# source_eagle.net
KiCad netlist of a schematic drawn in EAGLE
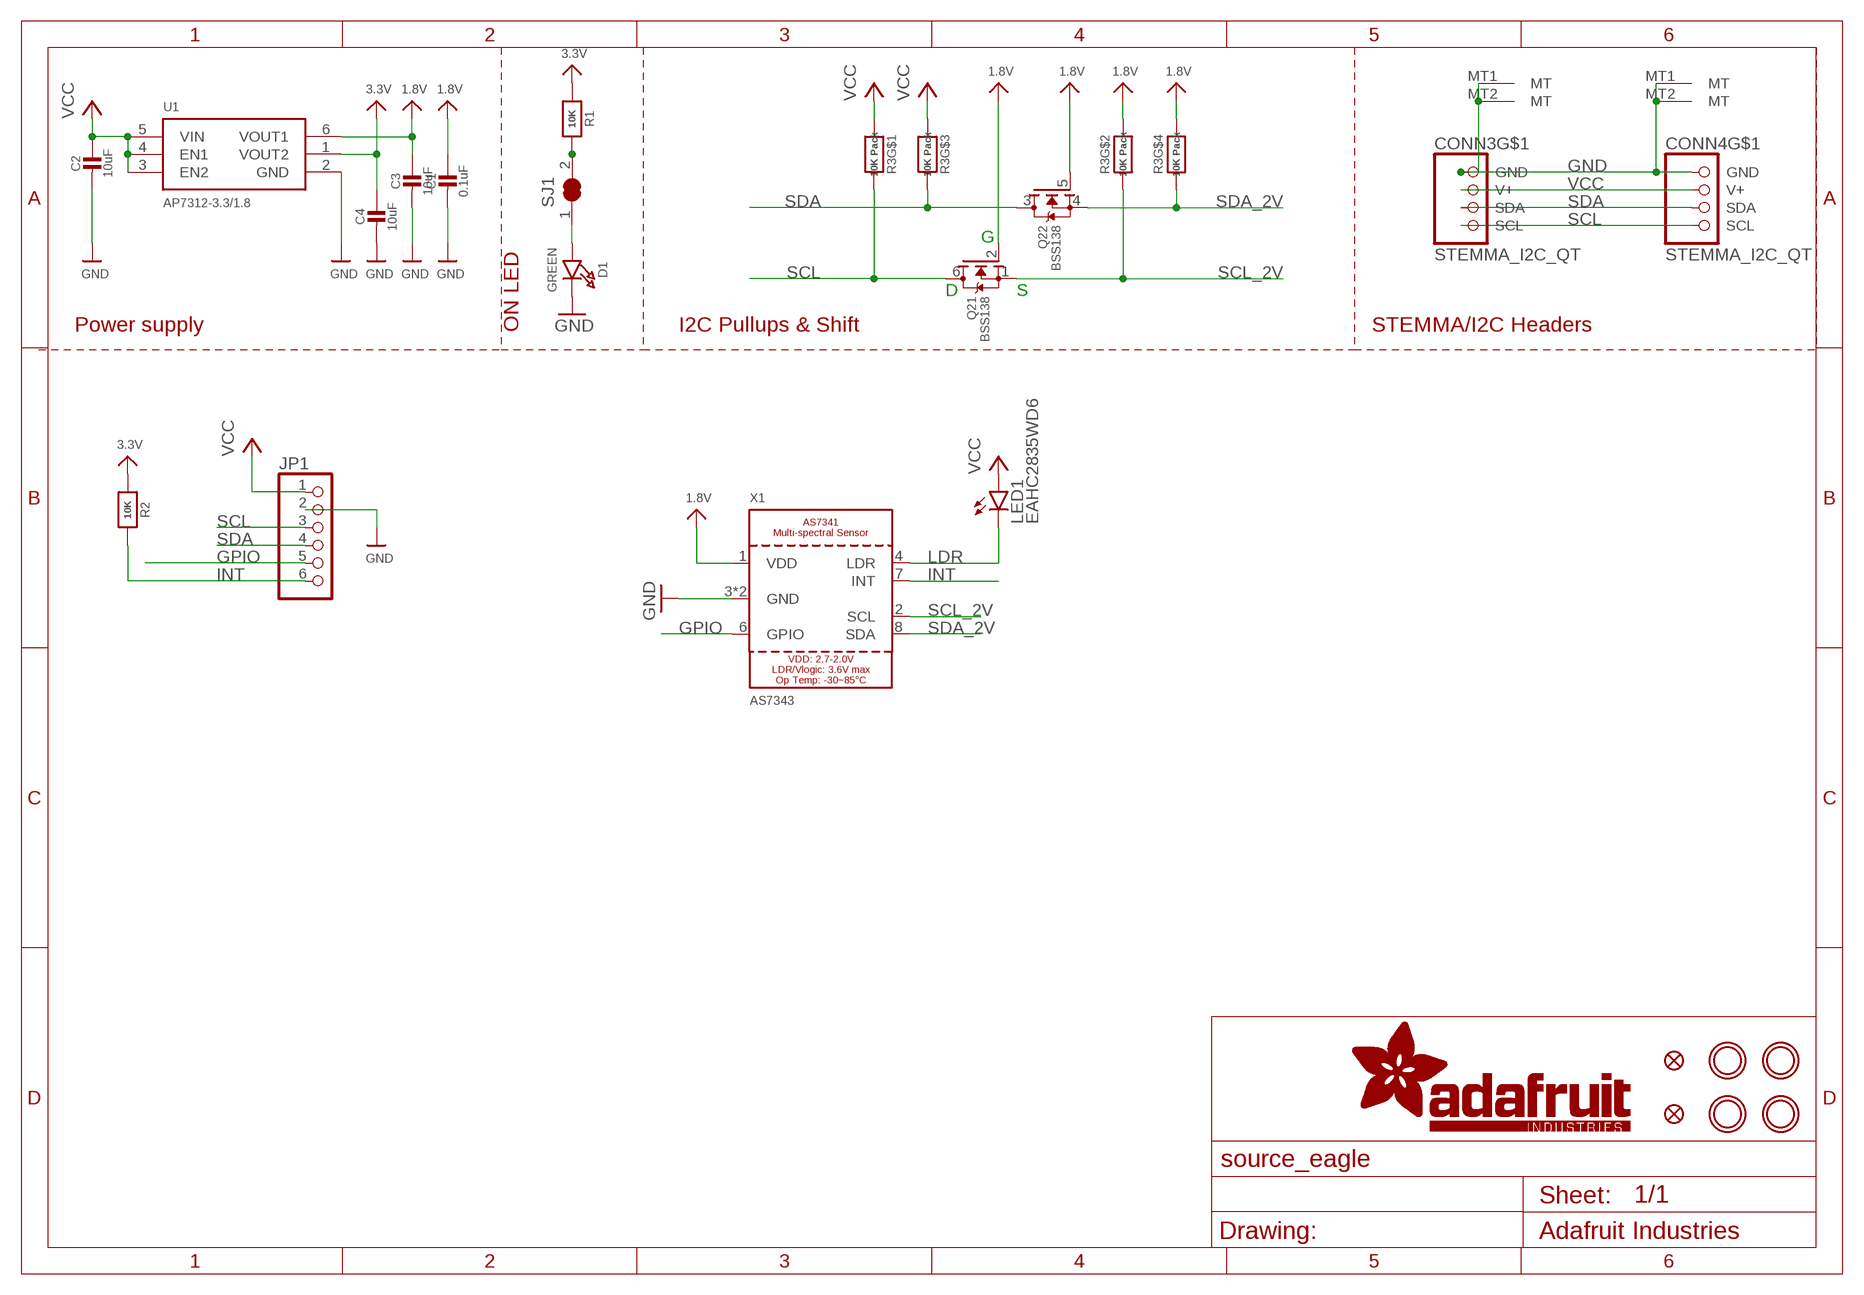
[diagram p0: schematic, sheet 1]

(export (version "E")
  (design (tool "Eeschema 10.0.6"))
  (components
    (comp (ref "C1")
      (value "0.1uF")
      (footprint "eagle-import:0603-NO")
      (libsource (lib "eagle-import") (part "CAP_CERAMIC0603_NO"))
    )
    (comp (ref "C2")
      (value "10uF")
      (footprint "eagle-import:0805-NO")
      (libsource (lib "eagle-import") (part "CAP_CERAMIC0805-NOOUTLINE"))
    )
    (comp (ref "C3")
      (value "10uF")
      (footprint "eagle-import:0805-NO")
      (libsource (lib "eagle-import") (part "CAP_CERAMIC0805-NOOUTLINE"))
    )
    (comp (ref "C4")
      (value "10uF")
      (footprint "eagle-import:0805-NO")
      (libsource (lib "eagle-import") (part "CAP_CERAMIC0805-NOOUTLINE"))
    )
    (comp (ref "CONN3")
      (value "STEMMA_I2C_QT")
      (footprint "eagle-import:JST_SH4")
      (libsource (lib "eagle-import") (part "STEMMA_I2C_QT"))
    )
    (comp (ref "CONN4")
      (value "STEMMA_I2C_QT")
      (footprint "eagle-import:JST_SH4")
      (libsource (lib "eagle-import") (part "STEMMA_I2C_QT"))
    )
    (comp (ref "D1")
      (value "GREEN")
      (footprint "eagle-import:CHIPLED_0603_NOOUTLINE")
      (libsource (lib "eagle-import") (part "LED0603_NOOUTLINE"))
    )
    (comp (ref "FID3")
      (value "FIDUCIAL_0.5MM")
      (footprint "eagle-import:FIDUCIAL_0.5MM")
      (libsource (lib "eagle-import") (part "FIDUCIAL_0.5MM"))
    )
    (comp (ref "FID4")
      (value "FIDUCIAL_0.5MM")
      (footprint "eagle-import:FIDUCIAL_0.5MM")
      (libsource (lib "eagle-import") (part "FIDUCIAL_0.5MM"))
    )
    (comp (ref "JP1")
      (value "HEADER-1X670MIL")
      (footprint "eagle-import:1X06_ROUND_70")
      (libsource (lib "eagle-import") (part "HEADER-1X670MIL"))
    )
    (comp (ref "LED1")
      (value "EAHC2835WD6")
      (footprint "eagle-import:KA-3528ASYC")
      (libsource (lib "eagle-import") (part "LEDKA-3528ASYC"))
    )
    (comp (ref "Q2")
      (value "BSS138")
      (footprint "eagle-import:SOT363")
      (libsource (lib "eagle-import") (part "MOSFET-N_DUAL"))
    )
    (comp (ref "R1")
      (value "10K")
      (footprint "eagle-import:0603-NO")
      (libsource (lib "eagle-import") (part "RESISTOR_0603_NOOUT"))
    )
    (comp (ref "R2")
      (value "10K")
      (footprint "eagle-import:0603-NO")
      (libsource (lib "eagle-import") (part "RESISTOR_0603_NOOUT"))
    )
    (comp (ref "R3")
      (value "10K Pack")
      (footprint "eagle-import:RESPACK_4X0603")
      (libsource (lib "eagle-import") (part "RESISTOR_4PACK"))
    )
    (comp (ref "SJ1")
      (value "SOLDERJUMPER_CLOSED")
      (footprint "eagle-import:SOLDERJUMPER_CLOSEDWIRE")
      (libsource (lib "eagle-import") (part "SOLDERJUMPER_CLOSED"))
    )
    (comp (ref "U$1")
      (value "MOUNTINGHOLE2.5")
      (footprint "eagle-import:MOUNTINGHOLE_2.5_PLATED")
      (libsource (lib "eagle-import") (part "MOUNTINGHOLE2.5"))
    )
    (comp (ref "U$17")
      (value "MOUNTINGHOLE2.5")
      (footprint "eagle-import:MOUNTINGHOLE_2.5_PLATED")
      (libsource (lib "eagle-import") (part "MOUNTINGHOLE2.5"))
    )
    (comp (ref "U$19")
      (value "MOUNTINGHOLE2.5")
      (footprint "eagle-import:MOUNTINGHOLE_2.5_PLATED")
      (libsource (lib "eagle-import") (part "MOUNTINGHOLE2.5"))
    )
    (comp (ref "U$21")
      (value "MOUNTINGHOLE2.5")
      (footprint "eagle-import:MOUNTINGHOLE_2.5_PLATED")
      (libsource (lib "eagle-import") (part "MOUNTINGHOLE2.5"))
    )
    (comp (ref "U1")
      (value "AP7312-3.3/1.8")
      (footprint "eagle-import:SOT23-6")
      (libsource (lib "eagle-import") (part "VREG_SOT23-6_DUALAP7312"))
    )
    (comp (ref "X1")
      (value "AS7343")
      (footprint "eagle-import:AS7341")
      (libsource (lib "eagle-import") (part "AS7341"))
    )
  )
  (nets
    (net (code "1") (name "/GPIO") (class "Default")
      (node (ref "JP1") (pin "5") (pinfunction "5_5") (pintype "passive"))
      (node (ref "X1") (pin "6") (pinfunction "GPIO_6") (pintype "power_in"))
    )
    (net (code "2") (name "/INT") (class "Default")
      (node (ref "JP1") (pin "6") (pinfunction "6_6") (pintype "passive"))
      (node (ref "R2") (pin "2") (pinfunction "2_2") (pintype "passive"))
      (node (ref "X1") (pin "7") (pinfunction "INT_7") (pintype "output"))
    )
    (net (code "3") (name "/LDR") (class "Default")
      (node (ref "LED1") (pin "C") (pinfunction "C_C") (pintype "passive"))
      (node (ref "X1") (pin "4") (pinfunction "LDR_4") (pintype "bidirectional"))
    )
    (net (code "4") (name "/SCL") (class "Default")
      (node (ref "CONN3") (pin "4") (pinfunction "SCL_4") (pintype "passive"))
      (node (ref "CONN4") (pin "4") (pinfunction "SCL_4") (pintype "passive"))
      (node (ref "JP1") (pin "3") (pinfunction "3_3") (pintype "passive"))
      (node (ref "Q2") (pin "6") (pinfunction "D_6") (pintype "bidirectional"))
      (node (ref "R3") (pin "8") (pinfunction "2_8") (pintype "passive"))
    )
    (net (code "5") (name "/SCL_2V") (class "Default")
      (node (ref "Q2") (pin "1") (pinfunction "S_1") (pintype "bidirectional"))
      (node (ref "R3") (pin "7") (pinfunction "2_7") (pintype "passive"))
      (node (ref "X1") (pin "2") (pinfunction "SCL_2") (pintype "input"))
    )
    (net (code "6") (name "/SDA") (class "Default")
      (node (ref "CONN3") (pin "3") (pinfunction "SDA_3") (pintype "passive"))
      (node (ref "CONN4") (pin "3") (pinfunction "SDA_3") (pintype "passive"))
      (node (ref "JP1") (pin "4") (pinfunction "4_4") (pintype "passive"))
      (node (ref "Q2") (pin "3") (pinfunction "D_3") (pintype "bidirectional"))
      (node (ref "R3") (pin "6") (pinfunction "2_6") (pintype "passive"))
    )
    (net (code "7") (name "/SDA_2V") (class "Default")
      (node (ref "Q2") (pin "4") (pinfunction "S_4") (pintype "bidirectional"))
      (node (ref "R3") (pin "5") (pinfunction "2_5") (pintype "passive"))
      (node (ref "X1") (pin "8") (pinfunction "SDA_8") (pintype "bidirectional"))
    )
    (net (code "8") (name "1.8V") (class "Default")
      (node (ref "C1") (pin "1") (pinfunction "1_1") (pintype "passive"))
      (node (ref "C3") (pin "1") (pinfunction "1_1") (pintype "passive"))
      (node (ref "Q2") (pin "2") (pinfunction "G_2") (pintype "bidirectional"))
      (node (ref "Q2") (pin "5") (pinfunction "G_5") (pintype "bidirectional"))
      (node (ref "R3") (pin "2") (pinfunction "1_2") (pintype "passive"))
      (node (ref "R3") (pin "4") (pinfunction "1_4") (pintype "passive"))
      (node (ref "U1") (pin "6") (pinfunction "VOUT1_6") (pintype "bidirectional"))
      (node (ref "X1") (pin "1") (pinfunction "VDD_1") (pintype "power_in"))
    )
    (net (code "9") (name "3.3V") (class "Default")
      (node (ref "C4") (pin "1") (pinfunction "1_1") (pintype "passive"))
      (node (ref "R1") (pin "1") (pinfunction "1_1") (pintype "passive"))
      (node (ref "R2") (pin "1") (pinfunction "1_1") (pintype "passive"))
      (node (ref "U1") (pin "1") (pinfunction "VOUT2_1") (pintype "bidirectional"))
    )
    (net (code "10") (name "GND") (class "Default")
      (node (ref "C1") (pin "2") (pinfunction "2_2") (pintype "passive"))
      (node (ref "C2") (pin "2") (pinfunction "2_2") (pintype "passive"))
      (node (ref "C3") (pin "2") (pinfunction "2_2") (pintype "passive"))
      (node (ref "C4") (pin "2") (pinfunction "2_2") (pintype "passive"))
      (node (ref "CONN3") (pin "1") (pinfunction "GND_1") (pintype "passive"))
      (node (ref "CONN3") (pin "MT1") (pinfunction "MT_MT1") (pintype "bidirectional"))
      (node (ref "CONN3") (pin "MT2") (pinfunction "MT_MT2") (pintype "bidirectional"))
      (node (ref "CONN4") (pin "1") (pinfunction "GND_1") (pintype "passive"))
      (node (ref "CONN4") (pin "MT1") (pinfunction "MT_MT1") (pintype "bidirectional"))
      (node (ref "CONN4") (pin "MT2") (pinfunction "MT_MT2") (pintype "bidirectional"))
      (node (ref "D1") (pin "C") (pinfunction "C_C") (pintype "passive"))
      (node (ref "JP1") (pin "2") (pinfunction "2_2") (pintype "passive"))
      (node (ref "U1") (pin "2") (pinfunction "GND_2") (pintype "bidirectional"))
      (node (ref "X1") (pin "3") (pinfunction "GND_3") (pintype "power_in"))
      (node (ref "X1") (pin "5") (pinfunction "GND_5") (pintype "power_in"))
    )
    (net (code "11") (name "Net-(D1-PadA)") (class "Default")
      (node (ref "D1") (pin "A") (pinfunction "A_A") (pintype "passive"))
      (node (ref "SJ1") (pin "1") (pinfunction "1_1") (pintype "passive"))
    )
    (net (code "12") (name "Net-(R1-Pad2)") (class "Default")
      (node (ref "R1") (pin "2") (pinfunction "2_2") (pintype "passive"))
      (node (ref "SJ1") (pin "2") (pinfunction "2_2") (pintype "passive"))
    )
    (net (code "13") (name "VCC") (class "Default")
      (node (ref "C2") (pin "1") (pinfunction "1_1") (pintype "passive"))
      (node (ref "CONN3") (pin "2") (pinfunction "V+_2") (pintype "passive"))
      (node (ref "CONN4") (pin "2") (pinfunction "V+_2") (pintype "passive"))
      (node (ref "JP1") (pin "1") (pinfunction "1_1") (pintype "passive"))
      (node (ref "LED1") (pin "A") (pinfunction "A_A") (pintype "passive"))
      (node (ref "R3") (pin "1") (pinfunction "1_1") (pintype "passive"))
      (node (ref "R3") (pin "3") (pinfunction "1_3") (pintype "passive"))
      (node (ref "U1") (pin "3") (pinfunction "EN2_3") (pintype "bidirectional"))
      (node (ref "U1") (pin "4") (pinfunction "EN1_4") (pintype "bidirectional"))
      (node (ref "U1") (pin "5") (pinfunction "VIN_5") (pintype "bidirectional"))
    )
  )
)
